# CAN_controller_main_dash.net
KiCad netlist of a schematic drawn in EAGLE
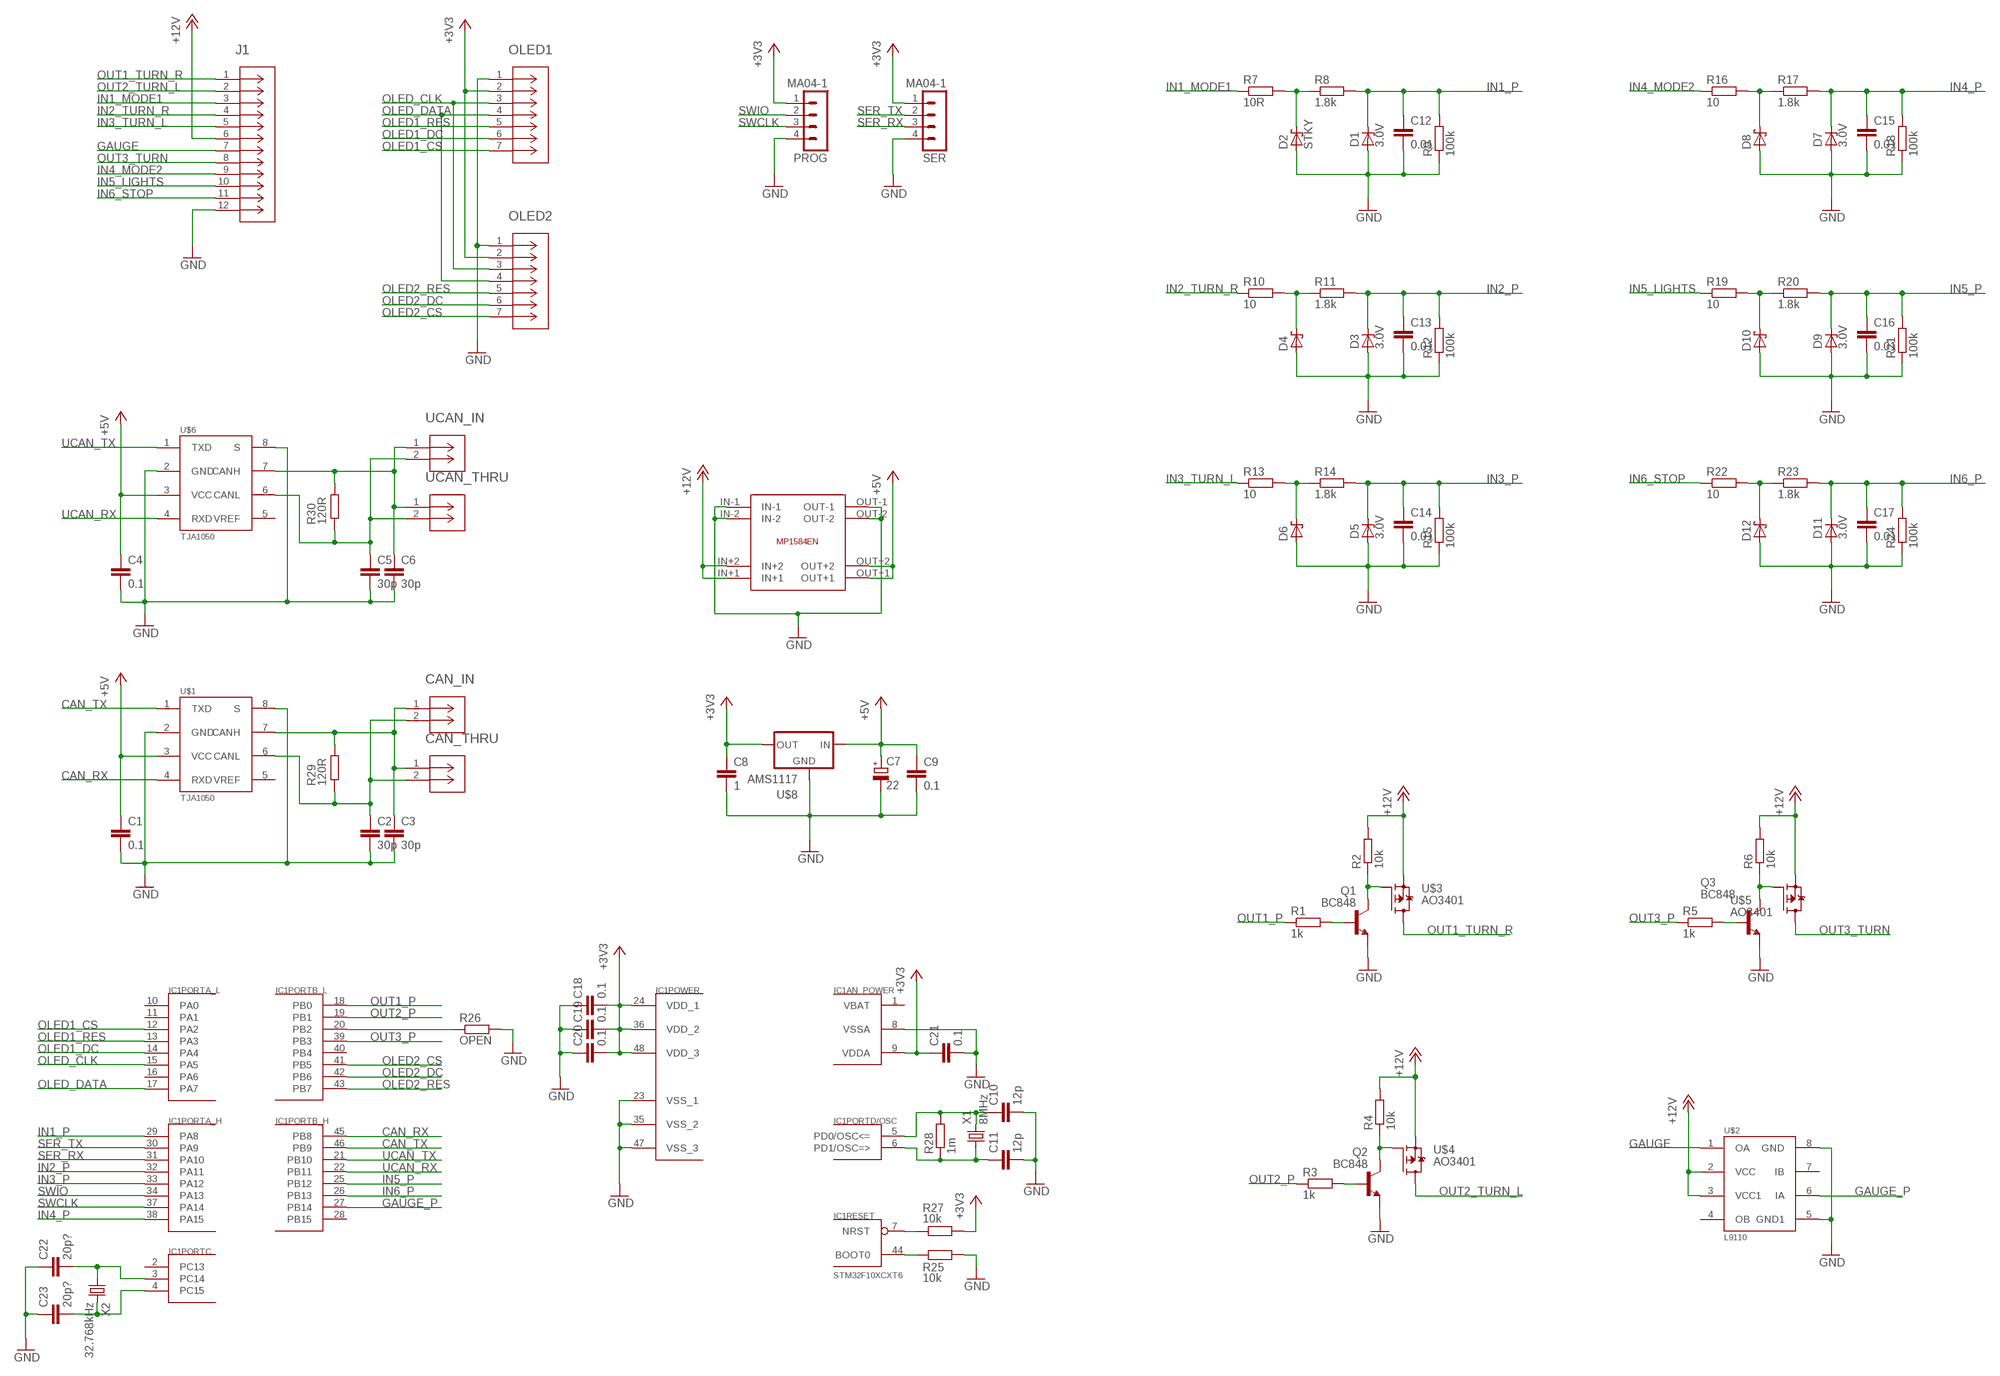
[diagram p0: schematic, sheet 1]

(export (version "E")
  (design (tool "Eeschema 10.0.6"))
  (components
    (comp (ref "C1")
      (value "0.1")
      (footprint "eagle-import:C0603")
      (libsource (lib "eagle-import") (part "C-EUC0603"))
    )
    (comp (ref "C2")
      (value "30p")
      (footprint "eagle-import:C0603")
      (libsource (lib "eagle-import") (part "C-EUC0603"))
    )
    (comp (ref "C3")
      (value "30p")
      (footprint "eagle-import:C0603")
      (libsource (lib "eagle-import") (part "C-EUC0603"))
    )
    (comp (ref "C4")
      (value "0.1")
      (footprint "eagle-import:C0603")
      (libsource (lib "eagle-import") (part "C-EUC0603"))
    )
    (comp (ref "C5")
      (value "30p")
      (footprint "eagle-import:C0603")
      (libsource (lib "eagle-import") (part "C-EUC0603"))
    )
    (comp (ref "C6")
      (value "30p")
      (footprint "eagle-import:C0603")
      (libsource (lib "eagle-import") (part "C-EUC0603"))
    )
    (comp (ref "C7")
      (value "22")
      (footprint "eagle-import:A_3216-18R")
      (libsource (lib "eagle-import") (part "CPOL-EUA/3216-18R"))
    )
    (comp (ref "C8")
      (value "1")
      (footprint "eagle-import:C0805")
      (libsource (lib "eagle-import") (part "C-EUC0805"))
    )
    (comp (ref "C9")
      (value "0.1")
      (footprint "eagle-import:C0603")
      (libsource (lib "eagle-import") (part "C-EUC0603"))
    )
    (comp (ref "C10")
      (value "12p")
      (footprint "eagle-import:C0603")
      (libsource (lib "eagle-import") (part "C-EUC0603"))
    )
    (comp (ref "C11")
      (value "12p")
      (footprint "eagle-import:C0603")
      (libsource (lib "eagle-import") (part "C-EUC0603"))
    )
    (comp (ref "C12")
      (value "0.01")
      (footprint "eagle-import:C0603")
      (libsource (lib "eagle-import") (part "C-EUC0603"))
    )
    (comp (ref "C13")
      (value "0.01")
      (footprint "eagle-import:C0603")
      (libsource (lib "eagle-import") (part "C-EUC0603"))
    )
    (comp (ref "C14")
      (value "0.01")
      (footprint "eagle-import:C0603")
      (libsource (lib "eagle-import") (part "C-EUC0603"))
    )
    (comp (ref "C15")
      (value "0.01")
      (footprint "eagle-import:C0603")
      (libsource (lib "eagle-import") (part "C-EUC0603"))
    )
    (comp (ref "C16")
      (value "0.01")
      (footprint "eagle-import:C0603")
      (libsource (lib "eagle-import") (part "C-EUC0603"))
    )
    (comp (ref "C17")
      (value "0.01")
      (footprint "eagle-import:C0603")
      (libsource (lib "eagle-import") (part "C-EUC0603"))
    )
    (comp (ref "C18")
      (value "0.1")
      (footprint "eagle-import:C0603")
      (libsource (lib "eagle-import") (part "C-EUC0603"))
    )
    (comp (ref "C19")
      (value "0.1")
      (footprint "eagle-import:C0603")
      (libsource (lib "eagle-import") (part "C-EUC0603"))
    )
    (comp (ref "C20")
      (value "0.1")
      (footprint "eagle-import:C0603")
      (libsource (lib "eagle-import") (part "C-EUC0603"))
    )
    (comp (ref "C21")
      (value "0.1")
      (footprint "eagle-import:C0603")
      (libsource (lib "eagle-import") (part "C-EUC0603"))
    )
    (comp (ref "C22")
      (value "20p?")
      (footprint "eagle-import:C0603")
      (libsource (lib "eagle-import") (part "C-EUC0603"))
    )
    (comp (ref "C23")
      (value "20p?")
      (footprint "eagle-import:C0603")
      (libsource (lib "eagle-import") (part "C-EUC0603"))
    )
    (comp (ref "CAN_IN")
      (value "CAN_IN")
      (footprint "eagle-import:CON_2068320202_MOL")
      (fields
        (field (name "MANUFACTURER_PART_NUMBER") "2068320202")
        (field (name "COPYRIGHT") "Copyright (C) 2022 Ultra Librarian. All rights reserved.")
      )
      (libsource (lib "eagle-import") (part "MOLEX_2068320202"))
    )
    (comp (ref "CAN_THRU")
      (value "MOLEX_2068320202")
      (footprint "eagle-import:CON_2068320202_MOL")
      (fields
        (field (name "MANUFACTURER_PART_NUMBER") "2068320202")
        (field (name "COPYRIGHT") "Copyright (C) 2022 Ultra Librarian. All rights reserved.")
      )
      (libsource (lib "eagle-import") (part "MOLEX_2068320202"))
    )
    (comp (ref "D1")
      (value "3.0V")
      (footprint "eagle-import:ZD0603")
      (libsource (lib "eagle-import") (part "DIODE_ZENER0603"))
    )
    (comp (ref "D2")
      (value "STKY")
      (footprint "eagle-import:ZD0603")
      (libsource (lib "eagle-import") (part "DIODE_SCHOTTKY"))
    )
    (comp (ref "D3")
      (value "3.0V")
      (footprint "eagle-import:ZD0603")
      (libsource (lib "eagle-import") (part "DIODE_ZENER0603"))
    )
    (comp (ref "D4")
      (value "DIODE_SCHOTTKY")
      (footprint "eagle-import:ZD0603")
      (libsource (lib "eagle-import") (part "DIODE_SCHOTTKY"))
    )
    (comp (ref "D5")
      (value "3.0V")
      (footprint "eagle-import:ZD0603")
      (libsource (lib "eagle-import") (part "DIODE_ZENER0603"))
    )
    (comp (ref "D6")
      (value "DIODE_SCHOTTKY")
      (footprint "eagle-import:ZD0603")
      (libsource (lib "eagle-import") (part "DIODE_SCHOTTKY"))
    )
    (comp (ref "D7")
      (value "3.0V")
      (footprint "eagle-import:ZD0603")
      (libsource (lib "eagle-import") (part "DIODE_ZENER0603"))
    )
    (comp (ref "D8")
      (value "DIODE_SCHOTTKY")
      (footprint "eagle-import:ZD0603")
      (libsource (lib "eagle-import") (part "DIODE_SCHOTTKY"))
    )
    (comp (ref "D9")
      (value "3.0V")
      (footprint "eagle-import:ZD0603")
      (libsource (lib "eagle-import") (part "DIODE_ZENER0603"))
    )
    (comp (ref "D10")
      (value "DIODE_SCHOTTKY")
      (footprint "eagle-import:ZD0603")
      (libsource (lib "eagle-import") (part "DIODE_SCHOTTKY"))
    )
    (comp (ref "D11")
      (value "3.0V")
      (footprint "eagle-import:ZD0603")
      (libsource (lib "eagle-import") (part "DIODE_ZENER0603"))
    )
    (comp (ref "D12")
      (value "DIODE_SCHOTTKY")
      (footprint "eagle-import:ZD0603")
      (libsource (lib "eagle-import") (part "DIODE_SCHOTTKY"))
    )
    (comp (ref "IC1")
      (value "STM32F10XCXT6")
      (footprint "eagle-import:TQFP48")
      (libsource (lib "eagle-import") (part "STM32F10XCXT6"))
    )
    (comp (ref "J1")
      (value "MOLEX_2068321202")
      (footprint "eagle-import:CON_2068321202_MOL")
      (fields
        (field (name "MANUFACTURER_PART_NUMBER") "2068321202")
        (field (name "COPYRIGHT") "Copyright (C) 2022 Ultra Librarian. All rights reserved.")
      )
      (libsource (lib "eagle-import") (part "MOLEX_2068321202"))
    )
    (comp (ref "OLED1")
      (value "MOLEX_1053091107")
      (footprint "eagle-import:CON_1053091107")
      (fields
        (field (name "MANUFACTURER_PART_NUMBER") "1053091107")
        (field (name "COPYRIGHT") "Copyright (C) 2022 Ultra Librarian. All rights reserved.")
      )
      (libsource (lib "eagle-import") (part "MOLEX_1053091107"))
    )
    (comp (ref "OLED2")
      (value "MOLEX_1053091107")
      (footprint "eagle-import:CON_1053091107")
      (fields
        (field (name "MANUFACTURER_PART_NUMBER") "1053091107")
        (field (name "COPYRIGHT") "Copyright (C) 2022 Ultra Librarian. All rights reserved.")
      )
      (libsource (lib "eagle-import") (part "MOLEX_1053091107"))
    )
    (comp (ref "PROG")
      (value "MA04-1")
      (footprint "eagle-import:1X04")
      (libsource (lib "eagle-import") (part "MA04-1"))
    )
    (comp (ref "Q1")
      (value "BC848")
      (footprint "eagle-import:SOT23")
      (libsource (lib "eagle-import") (part "BC848SMDALT1"))
    )
    (comp (ref "Q2")
      (value "BC848")
      (footprint "eagle-import:SOT23")
      (libsource (lib "eagle-import") (part "BC848SMDALT1"))
    )
    (comp (ref "Q3")
      (value "BC848")
      (footprint "eagle-import:SOT23")
      (libsource (lib "eagle-import") (part "BC848SMDALT1"))
    )
    (comp (ref "R1")
      (value "1k")
      (footprint "eagle-import:R0603")
      (libsource (lib "eagle-import") (part "resistor_348_R-EU_R0603"))
    )
    (comp (ref "R2")
      (value "10k")
      (footprint "eagle-import:R0603")
      (libsource (lib "eagle-import") (part "resistor_348_R-EU_R0603"))
    )
    (comp (ref "R3")
      (value "1k")
      (footprint "eagle-import:R0603")
      (libsource (lib "eagle-import") (part "resistor_348_R-EU_R0603"))
    )
    (comp (ref "R4")
      (value "10k")
      (footprint "eagle-import:R0603")
      (libsource (lib "eagle-import") (part "resistor_348_R-EU_R0603"))
    )
    (comp (ref "R5")
      (value "1k")
      (footprint "eagle-import:R0603")
      (libsource (lib "eagle-import") (part "resistor_348_R-EU_R0603"))
    )
    (comp (ref "R6")
      (value "10k")
      (footprint "eagle-import:R0603")
      (libsource (lib "eagle-import") (part "resistor_348_R-EU_R0603"))
    )
    (comp (ref "R7")
      (value "10R")
      (footprint "eagle-import:R0603")
      (libsource (lib "eagle-import") (part "R-EU_R0603"))
    )
    (comp (ref "R8")
      (value "1.8k")
      (footprint "eagle-import:R0603")
      (libsource (lib "eagle-import") (part "R-EU_R0603"))
    )
    (comp (ref "R9")
      (value "100k")
      (footprint "eagle-import:R0603")
      (libsource (lib "eagle-import") (part "R-EU_R0603"))
    )
    (comp (ref "R10")
      (value "10")
      (footprint "eagle-import:R0603")
      (libsource (lib "eagle-import") (part "R-EU_R0603"))
    )
    (comp (ref "R11")
      (value "1.8k")
      (footprint "eagle-import:R0603")
      (libsource (lib "eagle-import") (part "R-EU_R0603"))
    )
    (comp (ref "R12")
      (value "100k")
      (footprint "eagle-import:R0603")
      (libsource (lib "eagle-import") (part "R-EU_R0603"))
    )
    (comp (ref "R13")
      (value "10")
      (footprint "eagle-import:R0603")
      (libsource (lib "eagle-import") (part "R-EU_R0603"))
    )
    (comp (ref "R14")
      (value "1.8k")
      (footprint "eagle-import:R0603")
      (libsource (lib "eagle-import") (part "R-EU_R0603"))
    )
    (comp (ref "R15")
      (value "100k")
      (footprint "eagle-import:R0603")
      (libsource (lib "eagle-import") (part "R-EU_R0603"))
    )
    (comp (ref "R16")
      (value "10")
      (footprint "eagle-import:R0603")
      (libsource (lib "eagle-import") (part "R-EU_R0603"))
    )
    (comp (ref "R17")
      (value "1.8k")
      (footprint "eagle-import:R0603")
      (libsource (lib "eagle-import") (part "R-EU_R0603"))
    )
    (comp (ref "R18")
      (value "100k")
      (footprint "eagle-import:R0603")
      (libsource (lib "eagle-import") (part "R-EU_R0603"))
    )
    (comp (ref "R19")
      (value "10")
      (footprint "eagle-import:R0603")
      (libsource (lib "eagle-import") (part "R-EU_R0603"))
    )
    (comp (ref "R20")
      (value "1.8k")
      (footprint "eagle-import:R0603")
      (libsource (lib "eagle-import") (part "R-EU_R0603"))
    )
    (comp (ref "R21")
      (value "100k")
      (footprint "eagle-import:R0603")
      (libsource (lib "eagle-import") (part "R-EU_R0603"))
    )
    (comp (ref "R22")
      (value "10")
      (footprint "eagle-import:R0603")
      (libsource (lib "eagle-import") (part "R-EU_R0603"))
    )
    (comp (ref "R23")
      (value "1.8k")
      (footprint "eagle-import:R0603")
      (libsource (lib "eagle-import") (part "R-EU_R0603"))
    )
    (comp (ref "R24")
      (value "100k")
      (footprint "eagle-import:R0603")
      (libsource (lib "eagle-import") (part "R-EU_R0603"))
    )
    (comp (ref "R25")
      (value "10k")
      (footprint "eagle-import:R0603")
      (libsource (lib "eagle-import") (part "resistor_348_R-EU_R0603"))
    )
    (comp (ref "R26")
      (value "OPEN")
      (footprint "eagle-import:R0603")
      (libsource (lib "eagle-import") (part "resistor_348_R-EU_R0603"))
    )
    (comp (ref "R27")
      (value "10k")
      (footprint "eagle-import:R0603")
      (libsource (lib "eagle-import") (part "resistor_348_R-EU_R0603"))
    )
    (comp (ref "R28")
      (value "1m")
      (footprint "eagle-import:R0603")
      (libsource (lib "eagle-import") (part "resistor_348_R-EU_R0603"))
    )
    (comp (ref "R29")
      (value "120R")
      (footprint "eagle-import:R0603")
      (libsource (lib "eagle-import") (part "resistor_348_R-EU_R0603"))
    )
    (comp (ref "R30")
      (value "120R")
      (footprint "eagle-import:R0603")
      (libsource (lib "eagle-import") (part "resistor_348_R-EU_R0603"))
    )
    (comp (ref "SER")
      (value "MA04-1")
      (footprint "eagle-import:1X04")
      (libsource (lib "eagle-import") (part "MA04-1"))
    )
    (comp (ref "U$1")
      (value "TJA1050")
      (footprint "eagle-import:SO08")
      (libsource (lib "eagle-import") (part "TJA1050"))
    )
    (comp (ref "U$2")
      (value "L9110")
      (footprint "eagle-import:SO08")
      (libsource (lib "eagle-import") (part "L9110"))
    )
    (comp (ref "U$3")
      (value "AO3401")
      (footprint "eagle-import:SOT23")
      (libsource (lib "eagle-import") (part "AO3401"))
    )
    (comp (ref "U$4")
      (value "AO3401")
      (footprint "eagle-import:SOT23")
      (libsource (lib "eagle-import") (part "AO3401"))
    )
    (comp (ref "U$5")
      (value "AO3401")
      (footprint "eagle-import:SOT23")
      (libsource (lib "eagle-import") (part "AO3401"))
    )
    (comp (ref "U$6")
      (value "TJA1050")
      (footprint "eagle-import:SO08")
      (libsource (lib "eagle-import") (part "TJA1050"))
    )
    (comp (ref "U$7")
      (value "MP1584_DC-DC_MODULEMINI_22X17")
      (footprint "eagle-import:MP1584_DC-DC_MODULE")
      (libsource (lib "eagle-import") (part "MP1584_DC-DC_MODULEMINI_22X17"))
    )
    (comp (ref "U$8")
      (value "AMS1117")
      (footprint "eagle-import:SOT223-W")
      (libsource (lib "eagle-import") (part "AMS1117"))
    )
    (comp (ref "UCAN_IN")
      (value "MOLEX_2068320202")
      (footprint "eagle-import:CON_2068320202_MOL")
      (fields
        (field (name "MANUFACTURER_PART_NUMBER") "2068320202")
        (field (name "COPYRIGHT") "Copyright (C) 2022 Ultra Librarian. All rights reserved.")
      )
      (libsource (lib "eagle-import") (part "MOLEX_2068320202"))
    )
    (comp (ref "UCAN_THRU")
      (value "MOLEX_2068320202")
      (footprint "eagle-import:CON_2068320202_MOL")
      (fields
        (field (name "MANUFACTURER_PART_NUMBER") "2068320202")
        (field (name "COPYRIGHT") "Copyright (C) 2022 Ultra Librarian. All rights reserved.")
      )
      (libsource (lib "eagle-import") (part "MOLEX_2068320202"))
    )
    (comp (ref "X1")
      (value "8MHz")
      (footprint "eagle-import:XTAL-ECX-53")
      (libsource (lib "eagle-import") (part "CRYSTAL"))
    )
    (comp (ref "X2")
      (value "32.768kHz")
      (footprint "eagle-import:MM20SS")
      (libsource (lib "eagle-import") (part "CRYSTALMM20SS"))
    )
  )
  (nets
    (net (code "1") (name "+3V3") (class "Default")
      (node (ref "C18") (pin "2") (pinfunction "2_2") (pintype "passive"))
      (node (ref "C19") (pin "2") (pinfunction "2_2") (pintype "passive"))
      (node (ref "C20") (pin "2") (pinfunction "2_2") (pintype "passive"))
      (node (ref "C21") (pin "1") (pinfunction "1_1") (pintype "passive"))
      (node (ref "C8") (pin "1") (pinfunction "1_1") (pintype "passive"))
      (node (ref "IC1") (pin "24") (pinfunction "VDD_1_24") (pintype "power_in"))
      (node (ref "IC1") (pin "36") (pinfunction "VDD_2_36") (pintype "power_in"))
      (node (ref "IC1") (pin "48") (pinfunction "VDD_3_48") (pintype "power_in"))
      (node (ref "IC1") (pin "9") (pinfunction "VDDA_9") (pintype "power_in"))
      (node (ref "OLED1") (pin "2") (pinfunction "2_2") (pintype "passive"))
      (node (ref "OLED2") (pin "2") (pinfunction "2_2") (pintype "passive"))
      (node (ref "PROG") (pin "1") (pinfunction "1_1") (pintype "passive"))
      (node (ref "R27") (pin "2") (pinfunction "2_2") (pintype "passive"))
      (node (ref "SER") (pin "1") (pinfunction "1_1") (pintype "passive"))
      (node (ref "U$8") (pin "2") (pinfunction "OUT_2") (pintype "passive"))
    )
    (net (code "2") (name "+5V") (class "Default")
      (node (ref "C1") (pin "1") (pinfunction "1_1") (pintype "passive"))
      (node (ref "C4") (pin "1") (pinfunction "1_1") (pintype "passive"))
      (node (ref "C7") (pin "+") (pinfunction "+_+") (pintype "passive"))
      (node (ref "C9") (pin "1") (pinfunction "1_1") (pintype "passive"))
      (node (ref "U$1") (pin "3") (pinfunction "VCC_3") (pintype "bidirectional"))
      (node (ref "U$6") (pin "3") (pinfunction "VCC_3") (pintype "bidirectional"))
      (node (ref "U$7") (pin "OUT+1") (pinfunction "OUT+1_OUT+1") (pintype "bidirectional"))
      (node (ref "U$7") (pin "OUT+2") (pinfunction "OUT+2_OUT+2") (pintype "bidirectional"))
      (node (ref "U$8") (pin "3") (pinfunction "IN_3") (pintype "input"))
    )
    (net (code "3") (name "+12V") (class "Default")
      (node (ref "J1") (pin "6") (pinfunction "6_6") (pintype "passive"))
      (node (ref "R2") (pin "2") (pinfunction "2_2") (pintype "passive"))
      (node (ref "R4") (pin "2") (pinfunction "2_2") (pintype "passive"))
      (node (ref "R6") (pin "2") (pinfunction "2_2") (pintype "passive"))
      (node (ref "U$2") (pin "2") (pinfunction "VCC_2") (pintype "bidirectional"))
      (node (ref "U$2") (pin "3") (pinfunction "VCC1_3") (pintype "bidirectional"))
      (node (ref "U$3") (pin "2") (pinfunction "S_2") (pintype "passive"))
      (node (ref "U$4") (pin "2") (pinfunction "S_2") (pintype "passive"))
      (node (ref "U$5") (pin "2") (pinfunction "S_2") (pintype "passive"))
      (node (ref "U$7") (pin "IN+1") (pinfunction "IN+1_IN+1") (pintype "bidirectional"))
      (node (ref "U$7") (pin "IN+2") (pinfunction "IN+2_IN+2") (pintype "bidirectional"))
    )
    (net (code "4") (name "/CAN_RX") (class "Default")
      (node (ref "IC1") (pin "45") (pinfunction "PB8_45") (pintype "bidirectional"))
      (node (ref "U$1") (pin "4") (pinfunction "RXD_4") (pintype "bidirectional"))
    )
    (net (code "5") (name "/CAN_TX") (class "Default")
      (node (ref "IC1") (pin "46") (pinfunction "PB9_46") (pintype "bidirectional"))
      (node (ref "U$1") (pin "1") (pinfunction "TXD_1") (pintype "bidirectional"))
    )
    (net (code "6") (name "/GAUGE") (class "Default")
      (node (ref "J1") (pin "7") (pinfunction "7_7") (pintype "passive"))
      (node (ref "U$2") (pin "1") (pinfunction "OA_1") (pintype "bidirectional"))
    )
    (net (code "7") (name "/GAUGE_P") (class "Default")
      (node (ref "IC1") (pin "27") (pinfunction "PB14_27") (pintype "bidirectional"))
      (node (ref "U$2") (pin "6") (pinfunction "IA_6") (pintype "bidirectional"))
    )
    (net (code "8") (name "/IN1_MODE1") (class "Default")
      (node (ref "J1") (pin "3") (pinfunction "3_3") (pintype "passive"))
      (node (ref "R7") (pin "1") (pinfunction "1_1") (pintype "passive"))
    )
    (net (code "9") (name "/IN1_P") (class "Default")
      (node (ref "C12") (pin "1") (pinfunction "1_1") (pintype "passive"))
      (node (ref "D1") (pin "C") (pinfunction "C_C") (pintype "passive"))
      (node (ref "IC1") (pin "29") (pinfunction "PA8_29") (pintype "bidirectional"))
      (node (ref "R8") (pin "2") (pinfunction "2_2") (pintype "passive"))
      (node (ref "R9") (pin "2") (pinfunction "2_2") (pintype "passive"))
    )
    (net (code "10") (name "/IN2_P") (class "Default")
      (node (ref "C13") (pin "1") (pinfunction "1_1") (pintype "passive"))
      (node (ref "D3") (pin "C") (pinfunction "C_C") (pintype "passive"))
      (node (ref "IC1") (pin "32") (pinfunction "PA11_32") (pintype "bidirectional"))
      (node (ref "R11") (pin "2") (pinfunction "2_2") (pintype "passive"))
      (node (ref "R12") (pin "2") (pinfunction "2_2") (pintype "passive"))
    )
    (net (code "11") (name "/IN2_TURN_R") (class "Default")
      (node (ref "J1") (pin "4") (pinfunction "4_4") (pintype "passive"))
      (node (ref "R10") (pin "1") (pinfunction "1_1") (pintype "passive"))
    )
    (net (code "12") (name "/IN3_P") (class "Default")
      (node (ref "C14") (pin "1") (pinfunction "1_1") (pintype "passive"))
      (node (ref "D5") (pin "C") (pinfunction "C_C") (pintype "passive"))
      (node (ref "IC1") (pin "33") (pinfunction "PA12_33") (pintype "bidirectional"))
      (node (ref "R14") (pin "2") (pinfunction "2_2") (pintype "passive"))
      (node (ref "R15") (pin "2") (pinfunction "2_2") (pintype "passive"))
    )
    (net (code "13") (name "/IN3_TURN_L") (class "Default")
      (node (ref "J1") (pin "5") (pinfunction "5_5") (pintype "passive"))
      (node (ref "R13") (pin "1") (pinfunction "1_1") (pintype "passive"))
    )
    (net (code "14") (name "/IN4_MODE2") (class "Default")
      (node (ref "J1") (pin "9") (pinfunction "9_9") (pintype "passive"))
      (node (ref "R16") (pin "1") (pinfunction "1_1") (pintype "passive"))
    )
    (net (code "15") (name "/IN4_P") (class "Default")
      (node (ref "C15") (pin "1") (pinfunction "1_1") (pintype "passive"))
      (node (ref "D7") (pin "C") (pinfunction "C_C") (pintype "passive"))
      (node (ref "IC1") (pin "38") (pinfunction "PA15_38") (pintype "bidirectional"))
      (node (ref "R17") (pin "2") (pinfunction "2_2") (pintype "passive"))
      (node (ref "R18") (pin "2") (pinfunction "2_2") (pintype "passive"))
    )
    (net (code "16") (name "/IN5_LIGHTS") (class "Default")
      (node (ref "J1") (pin "10") (pinfunction "10_10") (pintype "passive"))
      (node (ref "R19") (pin "1") (pinfunction "1_1") (pintype "passive"))
    )
    (net (code "17") (name "/IN5_P") (class "Default")
      (node (ref "C16") (pin "1") (pinfunction "1_1") (pintype "passive"))
      (node (ref "D9") (pin "C") (pinfunction "C_C") (pintype "passive"))
      (node (ref "IC1") (pin "25") (pinfunction "PB12_25") (pintype "bidirectional"))
      (node (ref "R20") (pin "2") (pinfunction "2_2") (pintype "passive"))
      (node (ref "R21") (pin "2") (pinfunction "2_2") (pintype "passive"))
    )
    (net (code "18") (name "/IN6_P") (class "Default")
      (node (ref "C17") (pin "1") (pinfunction "1_1") (pintype "passive"))
      (node (ref "D11") (pin "C") (pinfunction "C_C") (pintype "passive"))
      (node (ref "IC1") (pin "26") (pinfunction "PB13_26") (pintype "bidirectional"))
      (node (ref "R23") (pin "2") (pinfunction "2_2") (pintype "passive"))
      (node (ref "R24") (pin "2") (pinfunction "2_2") (pintype "passive"))
    )
    (net (code "19") (name "/IN6_STOP") (class "Default")
      (node (ref "J1") (pin "11") (pinfunction "11_11") (pintype "passive"))
      (node (ref "R22") (pin "1") (pinfunction "1_1") (pintype "passive"))
    )
    (net (code "20") (name "/OLED1_CS") (class "Default")
      (node (ref "IC1") (pin "12") (pinfunction "PA2_12") (pintype "bidirectional"))
      (node (ref "OLED1") (pin "7") (pinfunction "7_7") (pintype "passive"))
    )
    (net (code "21") (name "/OLED1_DC") (class "Default")
      (node (ref "IC1") (pin "14") (pinfunction "PA4_14") (pintype "bidirectional"))
      (node (ref "OLED1") (pin "6") (pinfunction "6_6") (pintype "passive"))
    )
    (net (code "22") (name "/OLED1_RES") (class "Default")
      (node (ref "IC1") (pin "13") (pinfunction "PA3_13") (pintype "bidirectional"))
      (node (ref "OLED1") (pin "5") (pinfunction "5_5") (pintype "passive"))
    )
    (net (code "23") (name "/OLED2_CS") (class "Default")
      (node (ref "IC1") (pin "41") (pinfunction "PB5_41") (pintype "bidirectional"))
      (node (ref "OLED2") (pin "7") (pinfunction "7_7") (pintype "passive"))
    )
    (net (code "24") (name "/OLED2_DC") (class "Default")
      (node (ref "IC1") (pin "42") (pinfunction "PB6_42") (pintype "bidirectional"))
      (node (ref "OLED2") (pin "6") (pinfunction "6_6") (pintype "passive"))
    )
    (net (code "25") (name "/OLED2_RES") (class "Default")
      (node (ref "IC1") (pin "43") (pinfunction "PB7_43") (pintype "bidirectional"))
      (node (ref "OLED2") (pin "5") (pinfunction "5_5") (pintype "passive"))
    )
    (net (code "26") (name "/OLED_CLK") (class "Default")
      (node (ref "IC1") (pin "15") (pinfunction "PA5_15") (pintype "bidirectional"))
      (node (ref "OLED1") (pin "3") (pinfunction "3_3") (pintype "passive"))
      (node (ref "OLED2") (pin "3") (pinfunction "3_3") (pintype "passive"))
    )
    (net (code "27") (name "/OLED_DATA") (class "Default")
      (node (ref "IC1") (pin "17") (pinfunction "PA7_17") (pintype "bidirectional"))
      (node (ref "OLED1") (pin "4") (pinfunction "4_4") (pintype "passive"))
      (node (ref "OLED2") (pin "4") (pinfunction "4_4") (pintype "passive"))
    )
    (net (code "28") (name "/OUT1_P") (class "Default")
      (node (ref "IC1") (pin "18") (pinfunction "PB0_18") (pintype "bidirectional"))
      (node (ref "R1") (pin "1") (pinfunction "1_1") (pintype "passive"))
    )
    (net (code "29") (name "/OUT1_TURN_R") (class "Default")
      (node (ref "J1") (pin "1") (pinfunction "1_1") (pintype "passive"))
      (node (ref "U$3") (pin "3") (pinfunction "D_3") (pintype "passive"))
    )
    (net (code "30") (name "/OUT2_P") (class "Default")
      (node (ref "IC1") (pin "19") (pinfunction "PB1_19") (pintype "bidirectional"))
      (node (ref "R3") (pin "1") (pinfunction "1_1") (pintype "passive"))
    )
    (net (code "31") (name "/OUT2_TURN_L") (class "Default")
      (node (ref "J1") (pin "2") (pinfunction "2_2") (pintype "passive"))
      (node (ref "U$4") (pin "3") (pinfunction "D_3") (pintype "passive"))
    )
    (net (code "32") (name "/OUT3_P") (class "Default")
      (node (ref "IC1") (pin "39") (pinfunction "PB3_39") (pintype "bidirectional"))
      (node (ref "R5") (pin "1") (pinfunction "1_1") (pintype "passive"))
    )
    (net (code "33") (name "/OUT3_TURN") (class "Default")
      (node (ref "J1") (pin "8") (pinfunction "8_8") (pintype "passive"))
      (node (ref "U$5") (pin "3") (pinfunction "D_3") (pintype "passive"))
    )
    (net (code "34") (name "/SER_RX") (class "Default")
      (node (ref "IC1") (pin "31") (pinfunction "PA10_31") (pintype "bidirectional"))
      (node (ref "SER") (pin "3") (pinfunction "3_3") (pintype "passive"))
    )
    (net (code "35") (name "/SER_TX") (class "Default")
      (node (ref "IC1") (pin "30") (pinfunction "PA9_30") (pintype "bidirectional"))
      (node (ref "SER") (pin "2") (pinfunction "2_2") (pintype "passive"))
    )
    (net (code "36") (name "/SWCLK") (class "Default")
      (node (ref "IC1") (pin "37") (pinfunction "PA14_37") (pintype "bidirectional"))
      (node (ref "PROG") (pin "3") (pinfunction "3_3") (pintype "passive"))
    )
    (net (code "37") (name "/SWIO") (class "Default")
      (node (ref "IC1") (pin "34") (pinfunction "PA13_34") (pintype "bidirectional"))
      (node (ref "PROG") (pin "2") (pinfunction "2_2") (pintype "passive"))
    )
    (net (code "38") (name "/UCAN_RX") (class "Default")
      (node (ref "IC1") (pin "22") (pinfunction "PB11_22") (pintype "bidirectional"))
      (node (ref "U$6") (pin "4") (pinfunction "RXD_4") (pintype "bidirectional"))
    )
    (net (code "39") (name "/UCAN_TX") (class "Default")
      (node (ref "IC1") (pin "21") (pinfunction "PB10_21") (pintype "bidirectional"))
      (node (ref "U$6") (pin "1") (pinfunction "TXD_1") (pintype "bidirectional"))
    )
    (net (code "40") (name "/VBAT") (class "Default")
      (node (ref "IC1") (pin "1") (pinfunction "VBAT_1") (pintype "power_in"))
    )
    (net (code "41") (name "GND") (class "Default")
      (node (ref "C1") (pin "2") (pinfunction "2_2") (pintype "passive"))
      (node (ref "C10") (pin "2") (pinfunction "2_2") (pintype "passive"))
      (node (ref "C11") (pin "2") (pinfunction "2_2") (pintype "passive"))
      (node (ref "C12") (pin "2") (pinfunction "2_2") (pintype "passive"))
      (node (ref "C13") (pin "2") (pinfunction "2_2") (pintype "passive"))
      (node (ref "C14") (pin "2") (pinfunction "2_2") (pintype "passive"))
      (node (ref "C15") (pin "2") (pinfunction "2_2") (pintype "passive"))
      (node (ref "C16") (pin "2") (pinfunction "2_2") (pintype "passive"))
      (node (ref "C17") (pin "2") (pinfunction "2_2") (pintype "passive"))
      (node (ref "C18") (pin "1") (pinfunction "1_1") (pintype "passive"))
      (node (ref "C19") (pin "1") (pinfunction "1_1") (pintype "passive"))
      (node (ref "C2") (pin "2") (pinfunction "2_2") (pintype "passive"))
      (node (ref "C20") (pin "1") (pinfunction "1_1") (pintype "passive"))
      (node (ref "C21") (pin "2") (pinfunction "2_2") (pintype "passive"))
      (node (ref "C22") (pin "1") (pinfunction "1_1") (pintype "passive"))
      (node (ref "C23") (pin "1") (pinfunction "1_1") (pintype "passive"))
      (node (ref "C3") (pin "2") (pinfunction "2_2") (pintype "passive"))
      (node (ref "C4") (pin "2") (pinfunction "2_2") (pintype "passive"))
      (node (ref "C5") (pin "2") (pinfunction "2_2") (pintype "passive"))
      (node (ref "C6") (pin "2") (pinfunction "2_2") (pintype "passive"))
      (node (ref "C7") (pin "-") (pinfunction "-_-") (pintype "passive"))
      (node (ref "C8") (pin "2") (pinfunction "2_2") (pintype "passive"))
      (node (ref "C9") (pin "2") (pinfunction "2_2") (pintype "passive"))
      (node (ref "D1") (pin "A") (pinfunction "A_A") (pintype "passive"))
      (node (ref "D10") (pin "A") (pinfunction "A_A") (pintype "passive"))
      (node (ref "D11") (pin "A") (pinfunction "A_A") (pintype "passive"))
      (node (ref "D12") (pin "A") (pinfunction "A_A") (pintype "passive"))
      (node (ref "D2") (pin "A") (pinfunction "A_A") (pintype "passive"))
      (node (ref "D3") (pin "A") (pinfunction "A_A") (pintype "passive"))
      (node (ref "D4") (pin "A") (pinfunction "A_A") (pintype "passive"))
      (node (ref "D5") (pin "A") (pinfunction "A_A") (pintype "passive"))
      (node (ref "D6") (pin "A") (pinfunction "A_A") (pintype "passive"))
      (node (ref "D7") (pin "A") (pinfunction "A_A") (pintype "passive"))
      (node (ref "D8") (pin "A") (pinfunction "A_A") (pintype "passive"))
      (node (ref "D9") (pin "A") (pinfunction "A_A") (pintype "passive"))
      (node (ref "IC1") (pin "23") (pinfunction "VSS_1_23") (pintype "power_in"))
      (node (ref "IC1") (pin "35") (pinfunction "VSS_2_35") (pintype "power_in"))
      (node (ref "IC1") (pin "47") (pinfunction "VSS_3_47") (pintype "power_in"))
      (node (ref "IC1") (pin "8") (pinfunction "VSSA_8") (pintype "power_in"))
      (node (ref "J1") (pin "12") (pinfunction "12_12") (pintype "passive"))
      (node (ref "OLED1") (pin "1") (pinfunction "1_1") (pintype "passive"))
      (node (ref "OLED2") (pin "1") (pinfunction "1_1") (pintype "passive"))
      (node (ref "PROG") (pin "4") (pinfunction "4_4") (pintype "passive"))
      (node (ref "Q1") (pin "2") (pinfunction "E_2") (pintype "passive"))
      (node (ref "Q2") (pin "2") (pinfunction "E_2") (pintype "passive"))
      (node (ref "Q3") (pin "2") (pinfunction "E_2") (pintype "passive"))
      (node (ref "R12") (pin "1") (pinfunction "1_1") (pintype "passive"))
      (node (ref "R15") (pin "1") (pinfunction "1_1") (pintype "passive"))
      (node (ref "R18") (pin "1") (pinfunction "1_1") (pintype "passive"))
      (node (ref "R21") (pin "1") (pinfunction "1_1") (pintype "passive"))
      (node (ref "R24") (pin "1") (pinfunction "1_1") (pintype "passive"))
      (node (ref "R25") (pin "2") (pinfunction "2_2") (pintype "passive"))
      (node (ref "R26") (pin "2") (pinfunction "2_2") (pintype "passive"))
      (node (ref "R9") (pin "1") (pinfunction "1_1") (pintype "passive"))
      (node (ref "SER") (pin "4") (pinfunction "4_4") (pintype "passive"))
      (node (ref "U$1") (pin "2") (pinfunction "GND_2") (pintype "bidirectional"))
      (node (ref "U$1") (pin "8") (pinfunction "S_8") (pintype "bidirectional"))
      (node (ref "U$2") (pin "5") (pinfunction "GND1_5") (pintype "bidirectional"))
      (node (ref "U$2") (pin "8") (pinfunction "GND_8") (pintype "bidirectional"))
      (node (ref "U$6") (pin "2") (pinfunction "GND_2") (pintype "bidirectional"))
      (node (ref "U$6") (pin "8") (pinfunction "S_8") (pintype "bidirectional"))
      (node (ref "U$7") (pin "IN-1") (pinfunction "IN-1_IN-1") (pintype "bidirectional"))
      (node (ref "U$7") (pin "IN-2") (pinfunction "IN-2_IN-2") (pintype "bidirectional"))
      (node (ref "U$7") (pin "OUT-1") (pinfunction "OUT-1_OUT-1") (pintype "bidirectional"))
      (node (ref "U$7") (pin "OUT-2") (pinfunction "OUT-2_OUT-2") (pintype "bidirectional"))
      (node (ref "U$8") (pin "1") (pinfunction "GND_1") (pintype "input"))
    )
    (net (code "42") (name "Net-(D2-PadC)") (class "Default")
      (node (ref "D2") (pin "C") (pinfunction "C_C") (pintype "passive"))
      (node (ref "R7") (pin "2") (pinfunction "2_2") (pintype "passive"))
      (node (ref "R8") (pin "1") (pinfunction "1_1") (pintype "passive"))
    )
    (net (code "43") (name "Net-(D4-PadC)") (class "Default")
      (node (ref "D4") (pin "C") (pinfunction "C_C") (pintype "passive"))
      (node (ref "R10") (pin "2") (pinfunction "2_2") (pintype "passive"))
      (node (ref "R11") (pin "1") (pinfunction "1_1") (pintype "passive"))
    )
    (net (code "44") (name "Net-(D6-PadC)") (class "Default")
      (node (ref "D6") (pin "C") (pinfunction "C_C") (pintype "passive"))
      (node (ref "R13") (pin "2") (pinfunction "2_2") (pintype "passive"))
      (node (ref "R14") (pin "1") (pinfunction "1_1") (pintype "passive"))
    )
    (net (code "45") (name "Net-(D8-PadC)") (class "Default")
      (node (ref "D8") (pin "C") (pinfunction "C_C") (pintype "passive"))
      (node (ref "R16") (pin "2") (pinfunction "2_2") (pintype "passive"))
      (node (ref "R17") (pin "1") (pinfunction "1_1") (pintype "passive"))
    )
    (net (code "46") (name "Net-(D10-PadC)") (class "Default")
      (node (ref "D10") (pin "C") (pinfunction "C_C") (pintype "passive"))
      (node (ref "R19") (pin "2") (pinfunction "2_2") (pintype "passive"))
      (node (ref "R20") (pin "1") (pinfunction "1_1") (pintype "passive"))
    )
    (net (code "47") (name "Net-(D12-PadC)") (class "Default")
      (node (ref "D12") (pin "C") (pinfunction "C_C") (pintype "passive"))
      (node (ref "R22") (pin "2") (pinfunction "2_2") (pintype "passive"))
      (node (ref "R23") (pin "1") (pinfunction "1_1") (pintype "passive"))
    )
    (net (code "48") (name "Net-(IC1E-PB2)") (class "Default")
      (node (ref "IC1") (pin "20") (pinfunction "PB2_20") (pintype "bidirectional"))
      (node (ref "R26") (pin "1") (pinfunction "1_1") (pintype "passive"))
    )
    (net (code "49") (name "Net-(IC1F-PC14)") (class "Default")
      (node (ref "C22") (pin "2") (pinfunction "2_2") (pintype "passive"))
      (node (ref "IC1") (pin "3") (pinfunction "PC14_3") (pintype "bidirectional"))
      (node (ref "X2") (pin "1") (pinfunction "1_1") (pintype "passive"))
    )
    (net (code "50") (name "Net-(IC1F-PC15)") (class "Default")
      (node (ref "C23") (pin "2") (pinfunction "2_2") (pintype "passive"))
      (node (ref "IC1") (pin "4") (pinfunction "PC15_4") (pintype "bidirectional"))
      (node (ref "X2") (pin "4") (pinfunction "2_4") (pintype "passive"))
    )
    (net (code "51") (name "Net-(IC1G-PD0{slash}OSC<=)") (class "Default")
      (node (ref "C10") (pin "1") (pinfunction "1_1") (pintype "passive"))
      (node (ref "IC1") (pin "5") (pinfunction "PD0/OSC<=_5") (pintype "bidirectional"))
      (node (ref "R28") (pin "2") (pinfunction "2_2") (pintype "passive"))
      (node (ref "X1") (pin "2") (pinfunction "2_2") (pintype "passive"))
    )
    (net (code "52") (name "Net-(IC1G-PD1{slash}OSC=>)") (class "Default")
      (node (ref "C11") (pin "1") (pinfunction "1_1") (pintype "passive"))
      (node (ref "IC1") (pin "6") (pinfunction "PD1/OSC=>_6") (pintype "bidirectional"))
      (node (ref "R28") (pin "1") (pinfunction "1_1") (pintype "passive"))
      (node (ref "X1") (pin "1") (pinfunction "1_1") (pintype "passive"))
    )
    (net (code "53") (name "Net-(IC1I-BOOT0)") (class "Default")
      (node (ref "IC1") (pin "44") (pinfunction "BOOT0_44") (pintype "input"))
      (node (ref "R25") (pin "1") (pinfunction "1_1") (pintype "passive"))
    )
    (net (code "54") (name "Net-(IC1I-NRST)") (class "Default")
      (node (ref "IC1") (pin "7") (pinfunction "NRST_7") (pintype "input"))
      (node (ref "R27") (pin "1") (pinfunction "1_1") (pintype "passive"))
    )
    (net (code "55") (name "Net-(Q1-B)") (class "Default")
      (node (ref "Q1") (pin "1") (pinfunction "B_1") (pintype "passive"))
      (node (ref "R1") (pin "2") (pinfunction "2_2") (pintype "passive"))
    )
    (net (code "56") (name "Net-(Q1-C)") (class "Default")
      (node (ref "Q1") (pin "3") (pinfunction "C_3") (pintype "passive"))
      (node (ref "R2") (pin "1") (pinfunction "1_1") (pintype "passive"))
      (node (ref "U$3") (pin "1") (pinfunction "G_1") (pintype "passive"))
    )
    (net (code "57") (name "Net-(Q2-B)") (class "Default")
      (node (ref "Q2") (pin "1") (pinfunction "B_1") (pintype "passive"))
      (node (ref "R3") (pin "2") (pinfunction "2_2") (pintype "passive"))
    )
    (net (code "58") (name "Net-(Q2-C)") (class "Default")
      (node (ref "Q2") (pin "3") (pinfunction "C_3") (pintype "passive"))
      (node (ref "R4") (pin "1") (pinfunction "1_1") (pintype "passive"))
      (node (ref "U$4") (pin "1") (pinfunction "G_1") (pintype "passive"))
    )
    (net (code "59") (name "Net-(Q3-B)") (class "Default")
      (node (ref "Q3") (pin "1") (pinfunction "B_1") (pintype "passive"))
      (node (ref "R5") (pin "2") (pinfunction "2_2") (pintype "passive"))
    )
    (net (code "60") (name "Net-(Q3-C)") (class "Default")
      (node (ref "Q3") (pin "3") (pinfunction "C_3") (pintype "passive"))
      (node (ref "R6") (pin "1") (pinfunction "1_1") (pintype "passive"))
      (node (ref "U$5") (pin "1") (pinfunction "G_1") (pintype "passive"))
    )
    (net (code "61") (name "Net-(U$1-CANH)") (class "Default")
      (node (ref "C3") (pin "1") (pinfunction "1_1") (pintype "passive"))
      (node (ref "CAN_IN") (pin "1") (pinfunction "1_1") (pintype "passive"))
      (node (ref "CAN_THRU") (pin "1") (pinfunction "1_1") (pintype "passive"))
      (node (ref "R29") (pin "2") (pinfunction "2_2") (pintype "passive"))
      (node (ref "U$1") (pin "7") (pinfunction "CANH_7") (pintype "bidirectional"))
    )
    (net (code "62") (name "Net-(U$1-CANL)") (class "Default")
      (node (ref "C2") (pin "1") (pinfunction "1_1") (pintype "passive"))
      (node (ref "CAN_IN") (pin "2") (pinfunction "2_2") (pintype "passive"))
      (node (ref "CAN_THRU") (pin "2") (pinfunction "2_2") (pintype "passive"))
      (node (ref "R29") (pin "1") (pinfunction "1_1") (pintype "passive"))
      (node (ref "U$1") (pin "6") (pinfunction "CANL_6") (pintype "bidirectional"))
    )
    (net (code "63") (name "Net-(U$6-CANH)") (class "Default")
      (node (ref "C6") (pin "1") (pinfunction "1_1") (pintype "passive"))
      (node (ref "R30") (pin "2") (pinfunction "2_2") (pintype "passive"))
      (node (ref "U$6") (pin "7") (pinfunction "CANH_7") (pintype "bidirectional"))
      (node (ref "UCAN_IN") (pin "1") (pinfunction "1_1") (pintype "passive"))
      (node (ref "UCAN_THRU") (pin "1") (pinfunction "1_1") (pintype "passive"))
    )
    (net (code "64") (name "Net-(U$6-CANL)") (class "Default")
      (node (ref "C5") (pin "1") (pinfunction "1_1") (pintype "passive"))
      (node (ref "R30") (pin "1") (pinfunction "1_1") (pintype "passive"))
      (node (ref "U$6") (pin "6") (pinfunction "CANL_6") (pintype "bidirectional"))
      (node (ref "UCAN_IN") (pin "2") (pinfunction "2_2") (pintype "passive"))
      (node (ref "UCAN_THRU") (pin "2") (pinfunction "2_2") (pintype "passive"))
    )
    (net (code "65") (name "unconnected-(IC1C-PA0-Pad10)") (class "Default")
      (node (ref "IC1") (pin "10") (pinfunction "PA0_10") (pintype "bidirectional"))
    )
    (net (code "66") (name "unconnected-(IC1C-PA1-Pad11)") (class "Default")
      (node (ref "IC1") (pin "11") (pinfunction "PA1_11") (pintype "bidirectional"))
    )
    (net (code "67") (name "unconnected-(IC1C-PA6-Pad16)") (class "Default")
      (node (ref "IC1") (pin "16") (pinfunction "PA6_16") (pintype "bidirectional"))
    )
    (net (code "68") (name "unconnected-(IC1D-PB15-Pad28)") (class "Default")
      (node (ref "IC1") (pin "28") (pinfunction "PB15_28") (pintype "bidirectional"))
    )
    (net (code "69") (name "unconnected-(IC1E-PB4-Pad40)") (class "Default")
      (node (ref "IC1") (pin "40") (pinfunction "PB4_40") (pintype "bidirectional"))
    )
    (net (code "70") (name "unconnected-(IC1F-PC13-Pad2)") (class "Default")
      (node (ref "IC1") (pin "2") (pinfunction "PC13_2") (pintype "bidirectional"))
    )
    (net (code "71") (name "unconnected-(U$1-VREF-Pad5)") (class "Default")
      (node (ref "U$1") (pin "5") (pinfunction "VREF_5") (pintype "bidirectional"))
    )
    (net (code "72") (name "unconnected-(U$2-IB-Pad7)") (class "Default")
      (node (ref "U$2") (pin "7") (pinfunction "IB_7") (pintype "bidirectional"))
    )
    (net (code "73") (name "unconnected-(U$2-OB-Pad4)") (class "Default")
      (node (ref "U$2") (pin "4") (pinfunction "OB_4") (pintype "bidirectional"))
    )
    (net (code "74") (name "unconnected-(U$6-VREF-Pad5)") (class "Default")
      (node (ref "U$6") (pin "5") (pinfunction "VREF_5") (pintype "bidirectional"))
    )
  )
)
